# Xonik_Waveshaper_v1_0.net
KiCad netlist of a schematic drawn in EAGLE
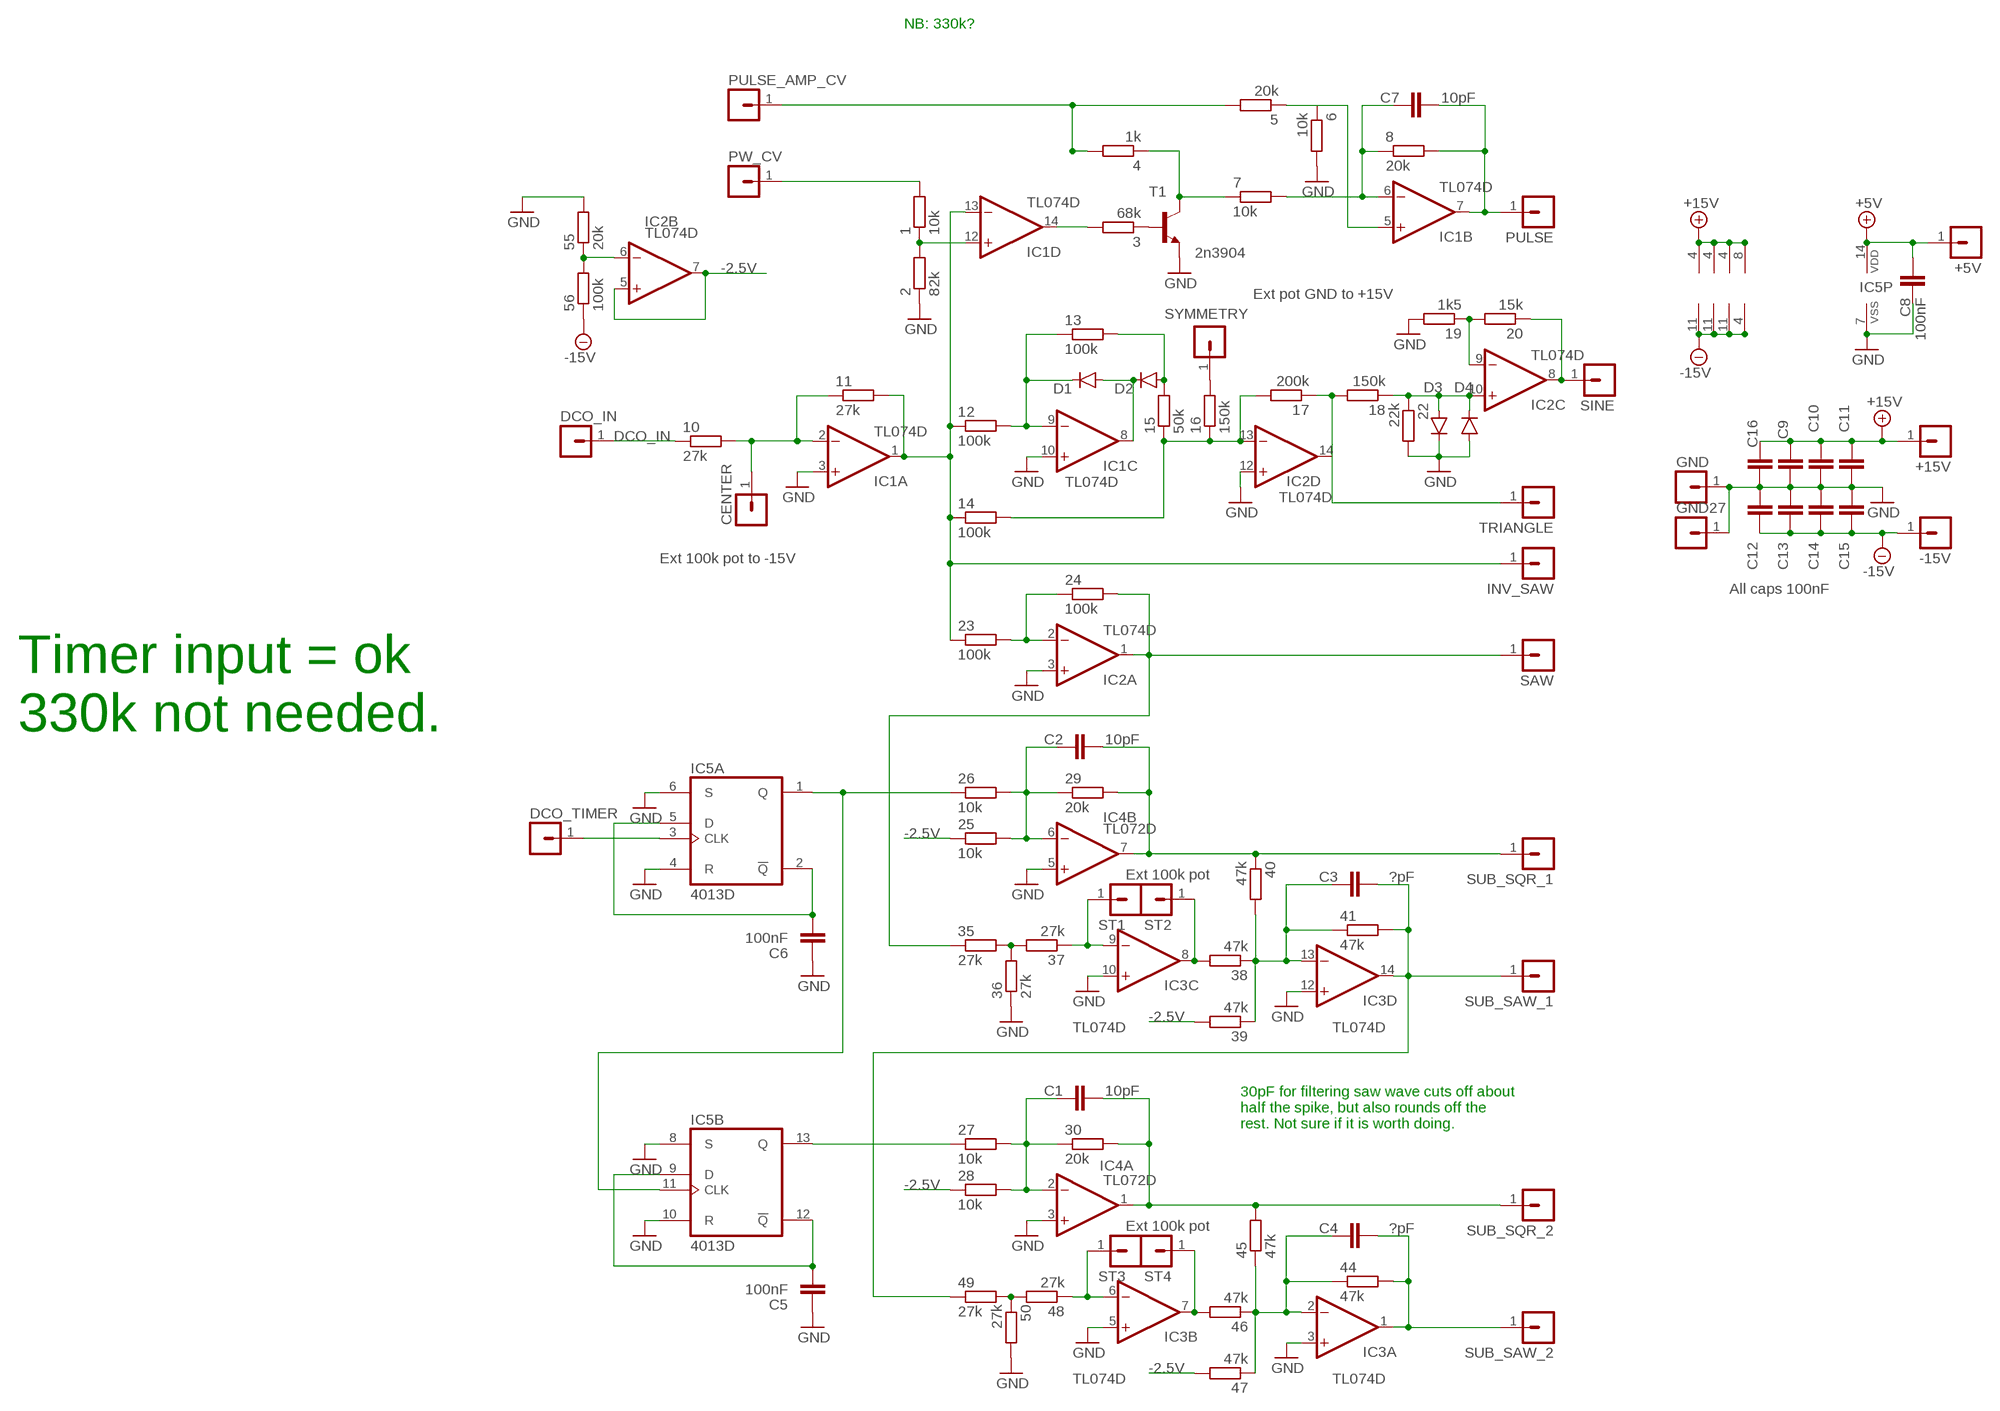
[diagram p0: schematic, sheet 1]

(export (version "E")
  (design (tool "Eeschema 10.0.6"))
  (components
    (comp (ref "+5V")
      (value "MA01-1JP")
      (footprint "eagle-import:SIP-PIN01-1J")
      (libsource (lib "eagle-import") (part "MA01-1JP"))
    )
    (comp (ref "+15V")
      (value "MA01-1JP")
      (footprint "eagle-import:SIP-PIN01-1J")
      (libsource (lib "eagle-import") (part "MA01-1JP"))
    )
    (comp (ref "-15V")
      (value "MA01-1JP")
      (footprint "eagle-import:SIP-PIN01-1J")
      (libsource (lib "eagle-import") (part "MA01-1JP"))
    )
    (comp (ref "1")
      (value "10k")
      (footprint "eagle-import:R0805")
      (libsource (lib "eagle-import") (part "R-EU_R0805"))
    )
    (comp (ref "2")
      (value "82k")
      (footprint "eagle-import:R0805")
      (libsource (lib "eagle-import") (part "R-EU_R0805"))
    )
    (comp (ref "3")
      (value "68k")
      (footprint "eagle-import:R0805")
      (libsource (lib "eagle-import") (part "R-EU_R0805"))
    )
    (comp (ref "4")
      (value "1k")
      (footprint "eagle-import:R0805")
      (libsource (lib "eagle-import") (part "R-EU_R0805"))
    )
    (comp (ref "5")
      (value "20k")
      (footprint "eagle-import:R0805")
      (libsource (lib "eagle-import") (part "R-EU_R0805"))
    )
    (comp (ref "6")
      (value "10k")
      (footprint "eagle-import:R0805")
      (libsource (lib "eagle-import") (part "R-EU_R0805"))
    )
    (comp (ref "7")
      (value "10k")
      (footprint "eagle-import:R0805")
      (libsource (lib "eagle-import") (part "R-EU_R0805"))
    )
    (comp (ref "8")
      (value "20k")
      (footprint "eagle-import:R0805")
      (libsource (lib "eagle-import") (part "R-EU_R0805"))
    )
    (comp (ref "10")
      (value "27k")
      (footprint "eagle-import:R0805")
      (libsource (lib "eagle-import") (part "R-EU_R0805"))
    )
    (comp (ref "11")
      (value "27k")
      (footprint "eagle-import:R0805")
      (libsource (lib "eagle-import") (part "R-EU_R0805"))
    )
    (comp (ref "12")
      (value "100k")
      (footprint "eagle-import:R0805")
      (libsource (lib "eagle-import") (part "R-EU_R0805"))
    )
    (comp (ref "13")
      (value "100k")
      (footprint "eagle-import:R0805")
      (libsource (lib "eagle-import") (part "R-EU_R0805"))
    )
    (comp (ref "14")
      (value "100k")
      (footprint "eagle-import:R0805")
      (libsource (lib "eagle-import") (part "R-EU_R0805"))
    )
    (comp (ref "15")
      (value "50k")
      (footprint "eagle-import:R0805")
      (libsource (lib "eagle-import") (part "R-EU_R0805"))
    )
    (comp (ref "16")
      (value "150k")
      (footprint "eagle-import:R0805")
      (libsource (lib "eagle-import") (part "R-EU_R0805"))
    )
    (comp (ref "17")
      (value "200k")
      (footprint "eagle-import:R0805")
      (libsource (lib "eagle-import") (part "R-EU_R0805"))
    )
    (comp (ref "18")
      (value "150k")
      (footprint "eagle-import:R0805")
      (libsource (lib "eagle-import") (part "R-EU_R0805"))
    )
    (comp (ref "19")
      (value "1k5")
      (footprint "eagle-import:R0805")
      (libsource (lib "eagle-import") (part "R-EU_R0805"))
    )
    (comp (ref "20")
      (value "15k")
      (footprint "eagle-import:R0805")
      (libsource (lib "eagle-import") (part "R-EU_R0805"))
    )
    (comp (ref "22")
      (value "22k")
      (footprint "eagle-import:R0805")
      (libsource (lib "eagle-import") (part "R-EU_R0805"))
    )
    (comp (ref "23")
      (value "100k")
      (footprint "eagle-import:R0805")
      (libsource (lib "eagle-import") (part "R-EU_R0805"))
    )
    (comp (ref "24")
      (value "100k")
      (footprint "eagle-import:R0805")
      (libsource (lib "eagle-import") (part "R-EU_R0805"))
    )
    (comp (ref "25")
      (value "10k")
      (footprint "eagle-import:R0805")
      (libsource (lib "eagle-import") (part "R-EU_R0805"))
    )
    (comp (ref "26")
      (value "10k")
      (footprint "eagle-import:R0805")
      (libsource (lib "eagle-import") (part "R-EU_R0805"))
    )
    (comp (ref "27")
      (value "10k")
      (footprint "eagle-import:R0805")
      (libsource (lib "eagle-import") (part "R-EU_R0805"))
    )
    (comp (ref "28")
      (value "10k")
      (footprint "eagle-import:R0805")
      (libsource (lib "eagle-import") (part "R-EU_R0805"))
    )
    (comp (ref "29")
      (value "20k")
      (footprint "eagle-import:R0805")
      (libsource (lib "eagle-import") (part "R-EU_R0805"))
    )
    (comp (ref "30")
      (value "20k")
      (footprint "eagle-import:R0805")
      (libsource (lib "eagle-import") (part "R-EU_R0805"))
    )
    (comp (ref "35")
      (value "27k")
      (footprint "eagle-import:R0805")
      (libsource (lib "eagle-import") (part "R-EU_R0805"))
    )
    (comp (ref "36")
      (value "27k")
      (footprint "eagle-import:R0805")
      (libsource (lib "eagle-import") (part "R-EU_R0805"))
    )
    (comp (ref "37")
      (value "27k")
      (footprint "eagle-import:R0805")
      (libsource (lib "eagle-import") (part "R-EU_R0805"))
    )
    (comp (ref "38")
      (value "47k")
      (footprint "eagle-import:R0805")
      (libsource (lib "eagle-import") (part "R-EU_R0805"))
    )
    (comp (ref "39")
      (value "47k")
      (footprint "eagle-import:R0805")
      (libsource (lib "eagle-import") (part "R-EU_R0805"))
    )
    (comp (ref "40")
      (value "47k")
      (footprint "eagle-import:R0805")
      (libsource (lib "eagle-import") (part "R-EU_R0805"))
    )
    (comp (ref "41")
      (value "47k")
      (footprint "eagle-import:R0805")
      (libsource (lib "eagle-import") (part "R-EU_R0805"))
    )
    (comp (ref "44")
      (value "47k")
      (footprint "eagle-import:R0805")
      (libsource (lib "eagle-import") (part "R-EU_R0805"))
    )
    (comp (ref "45")
      (value "47k")
      (footprint "eagle-import:R0805")
      (libsource (lib "eagle-import") (part "R-EU_R0805"))
    )
    (comp (ref "46")
      (value "47k")
      (footprint "eagle-import:R0805")
      (libsource (lib "eagle-import") (part "R-EU_R0805"))
    )
    (comp (ref "47")
      (value "47k")
      (footprint "eagle-import:R0805")
      (libsource (lib "eagle-import") (part "R-EU_R0805"))
    )
    (comp (ref "48")
      (value "27k")
      (footprint "eagle-import:R0805")
      (libsource (lib "eagle-import") (part "R-EU_R0805"))
    )
    (comp (ref "49")
      (value "27k")
      (footprint "eagle-import:R0805")
      (libsource (lib "eagle-import") (part "R-EU_R0805"))
    )
    (comp (ref "50")
      (value "27k")
      (footprint "eagle-import:R0805")
      (libsource (lib "eagle-import") (part "R-EU_R0805"))
    )
    (comp (ref "55")
      (value "20k")
      (footprint "eagle-import:R0805")
      (libsource (lib "eagle-import") (part "R-EU_R0805"))
    )
    (comp (ref "56")
      (value "100k")
      (footprint "eagle-import:R0805")
      (libsource (lib "eagle-import") (part "R-EU_R0805"))
    )
    (comp (ref "C1")
      (value "10pF")
      (footprint "eagle-import:C0805")
      (libsource (lib "eagle-import") (part "C-EUC0805"))
    )
    (comp (ref "C2")
      (value "10pF")
      (footprint "eagle-import:C0805")
      (libsource (lib "eagle-import") (part "C-EUC0805"))
    )
    (comp (ref "C3")
      (value "?pF")
      (footprint "eagle-import:C0805")
      (libsource (lib "eagle-import") (part "C-EUC0805"))
    )
    (comp (ref "C4")
      (value "?pF")
      (footprint "eagle-import:C0805")
      (libsource (lib "eagle-import") (part "C-EUC0805"))
    )
    (comp (ref "C5")
      (value "100nF")
      (footprint "eagle-import:C0805")
      (libsource (lib "eagle-import") (part "C-EUC0805"))
    )
    (comp (ref "C6")
      (value "100nF")
      (footprint "eagle-import:C0805")
      (libsource (lib "eagle-import") (part "C-EUC0805"))
    )
    (comp (ref "C7")
      (value "10pF")
      (footprint "eagle-import:C0805")
      (libsource (lib "eagle-import") (part "C-EUC0805"))
    )
    (comp (ref "C8")
      (value "100nF")
      (footprint "eagle-import:C0805")
      (libsource (lib "eagle-import") (part "C-EUC0805"))
    )
    (comp (ref "C9")
      (value "100nF")
      (footprint "eagle-import:C0603K")
      (libsource (lib "eagle-import") (part "C-EUC0603K"))
    )
    (comp (ref "C10")
      (value "100nF")
      (footprint "eagle-import:C0603K")
      (libsource (lib "eagle-import") (part "C-EUC0603K"))
    )
    (comp (ref "C11")
      (value "100nF")
      (footprint "eagle-import:C0603K")
      (libsource (lib "eagle-import") (part "C-EUC0603K"))
    )
    (comp (ref "C12")
      (value "100nF")
      (footprint "eagle-import:C0603K")
      (libsource (lib "eagle-import") (part "C-EUC0603K"))
    )
    (comp (ref "C13")
      (value "100nF")
      (footprint "eagle-import:C0603K")
      (libsource (lib "eagle-import") (part "C-EUC0603K"))
    )
    (comp (ref "C14")
      (value "100nF")
      (footprint "eagle-import:C0603K")
      (libsource (lib "eagle-import") (part "C-EUC0603K"))
    )
    (comp (ref "C15")
      (value "100nF")
      (footprint "eagle-import:C0603K")
      (libsource (lib "eagle-import") (part "C-EUC0603K"))
    )
    (comp (ref "C16")
      (value "100nF")
      (footprint "eagle-import:C0603K")
      (libsource (lib "eagle-import") (part "C-EUC0603K"))
    )
    (comp (ref "CENTER")
      (value "MA01-1JP")
      (footprint "eagle-import:SIP-PIN01-1J")
      (libsource (lib "eagle-import") (part "MA01-1JP"))
    )
    (comp (ref "D1")
      (value "1N41480805")
      (footprint "eagle-import:D0805-J")
      (libsource (lib "eagle-import") (part "1N41480805"))
    )
    (comp (ref "D2")
      (value "1N41480805")
      (footprint "eagle-import:D0805-J")
      (libsource (lib "eagle-import") (part "1N41480805"))
    )
    (comp (ref "D3")
      (value "1N41480805")
      (footprint "eagle-import:D0805-J")
      (libsource (lib "eagle-import") (part "1N41480805"))
    )
    (comp (ref "D4")
      (value "1N41480805")
      (footprint "eagle-import:D0805-J")
      (libsource (lib "eagle-import") (part "1N41480805"))
    )
    (comp (ref "DCO_IN")
      (value "MA01-1JP")
      (footprint "eagle-import:SIP-PIN01-1J")
      (libsource (lib "eagle-import") (part "MA01-1JP"))
    )
    (comp (ref "DCO_TIMER")
      (value "MA01-1JP")
      (footprint "eagle-import:SIP-PIN01-1J")
      (libsource (lib "eagle-import") (part "MA01-1JP"))
    )
    (comp (ref "GND")
      (value "MA01-1JP")
      (footprint "eagle-import:SIP-PIN01-1J")
      (libsource (lib "eagle-import") (part "MA01-1JP"))
    )
    (comp (ref "GND27")
      (value "MA01-1JP")
      (footprint "eagle-import:SIP-PIN01-1J")
      (libsource (lib "eagle-import") (part "MA01-1JP"))
    )
    (comp (ref "IC1")
      (value "TL074D")
      (footprint "eagle-import:SO14")
      (libsource (lib "eagle-import") (part "TL074D"))
    )
    (comp (ref "IC2")
      (value "TL074D")
      (footprint "eagle-import:SO14")
      (libsource (lib "eagle-import") (part "TL074D"))
    )
    (comp (ref "IC3")
      (value "TL074D")
      (footprint "eagle-import:SO14")
      (libsource (lib "eagle-import") (part "TL074D"))
    )
    (comp (ref "IC4")
      (value "TL072D")
      (footprint "eagle-import:SO08J")
      (libsource (lib "eagle-import") (part "TL072D"))
    )
    (comp (ref "IC5")
      (value "4013D")
      (footprint "eagle-import:SO14J")
      (libsource (lib "eagle-import") (part "4013D"))
    )
    (comp (ref "INV_SAW")
      (value "MA01-1JP")
      (footprint "eagle-import:SIP-PIN01-1J")
      (libsource (lib "eagle-import") (part "MA01-1JP"))
    )
    (comp (ref "PULSE")
      (value "MA01-1JP")
      (footprint "eagle-import:SIP-PIN01-1J")
      (libsource (lib "eagle-import") (part "MA01-1JP"))
    )
    (comp (ref "PULSE_AMP_CV")
      (value "MA01-1JP")
      (footprint "eagle-import:SIP-PIN01-1J")
      (libsource (lib "eagle-import") (part "MA01-1JP"))
    )
    (comp (ref "PW_CV")
      (value "MA01-1JP")
      (footprint "eagle-import:SIP-PIN01-1J")
      (libsource (lib "eagle-import") (part "MA01-1JP"))
    )
    (comp (ref "SAW")
      (value "MA01-1JP")
      (footprint "eagle-import:SIP-PIN01-1J")
      (libsource (lib "eagle-import") (part "MA01-1JP"))
    )
    (comp (ref "SINE")
      (value "MA01-1JP")
      (footprint "eagle-import:SIP-PIN01-1J")
      (libsource (lib "eagle-import") (part "MA01-1JP"))
    )
    (comp (ref "ST1")
      (value "MA01-1JP")
      (footprint "eagle-import:SIP-PIN01-1J")
      (libsource (lib "eagle-import") (part "MA01-1JP"))
    )
    (comp (ref "ST2")
      (value "MA01-1JP")
      (footprint "eagle-import:SIP-PIN01-1J")
      (libsource (lib "eagle-import") (part "MA01-1JP"))
    )
    (comp (ref "ST3")
      (value "MA01-1JP")
      (footprint "eagle-import:SIP-PIN01-1J")
      (libsource (lib "eagle-import") (part "MA01-1JP"))
    )
    (comp (ref "ST4")
      (value "MA01-1JP")
      (footprint "eagle-import:SIP-PIN01-1J")
      (libsource (lib "eagle-import") (part "MA01-1JP"))
    )
    (comp (ref "SUB_SAW_1")
      (value "MA01-1JP")
      (footprint "eagle-import:SIP-PIN01-1J")
      (libsource (lib "eagle-import") (part "MA01-1JP"))
    )
    (comp (ref "SUB_SAW_2")
      (value "MA01-1JP")
      (footprint "eagle-import:SIP-PIN01-1J")
      (libsource (lib "eagle-import") (part "MA01-1JP"))
    )
    (comp (ref "SUB_SQR_1")
      (value "MA01-1JP")
      (footprint "eagle-import:SIP-PIN01-1J")
      (libsource (lib "eagle-import") (part "MA01-1JP"))
    )
    (comp (ref "SUB_SQR_2")
      (value "MA01-1JP")
      (footprint "eagle-import:SIP-PIN01-1J")
      (libsource (lib "eagle-import") (part "MA01-1JP"))
    )
    (comp (ref "SYMMETRY")
      (value "MA01-1JP")
      (footprint "eagle-import:SIP-PIN01-1J")
      (libsource (lib "eagle-import") (part "MA01-1JP"))
    )
    (comp (ref "T1")
      (value "2n3904")
      (footprint "eagle-import:SOT23-BEC")
      (libsource (lib "eagle-import") (part "-NPN-SOT23-BECMMBT3904LT1"))
    )
    (comp (ref "TRIANGLE")
      (value "MA01-1JP")
      (footprint "eagle-import:SIP-PIN01-1J")
      (libsource (lib "eagle-import") (part "MA01-1JP"))
    )
  )
  (nets
    (net (code "1") (name "+5V") (class "Default")
      (node (ref "+5V") (pin "1") (pinfunction "1_1") (pintype "passive"))
      (node (ref "C8") (pin "2") (pinfunction "2_2") (pintype "passive"))
      (node (ref "IC5") (pin "14") (pinfunction "VDD_14") (pintype "power_in"))
    )
    (net (code "2") (name "+15V") (class "Default")
      (node (ref "+15V") (pin "1") (pinfunction "1_1") (pintype "passive"))
      (node (ref "C10") (pin "2") (pinfunction "2_2") (pintype "passive"))
      (node (ref "C11") (pin "2") (pinfunction "2_2") (pintype "passive"))
      (node (ref "C16") (pin "2") (pinfunction "2_2") (pintype "passive"))
      (node (ref "C9") (pin "2") (pinfunction "2_2") (pintype "passive"))
      (node (ref "IC1") (pin "4") (pinfunction "V+_4") (pintype "power_in"))
      (node (ref "IC2") (pin "4") (pinfunction "V+_4") (pintype "power_in"))
      (node (ref "IC3") (pin "4") (pinfunction "V+_4") (pintype "power_in"))
      (node (ref "IC4") (pin "8") (pinfunction "V+_8") (pintype "power_in"))
    )
    (net (code "3") (name "-15V") (class "Default")
      (node (ref "-15V") (pin "1") (pinfunction "1_1") (pintype "passive"))
      (node (ref "56") (pin "1") (pinfunction "1_1") (pintype "passive"))
      (node (ref "C12") (pin "1") (pinfunction "1_1") (pintype "passive"))
      (node (ref "C13") (pin "1") (pinfunction "1_1") (pintype "passive"))
      (node (ref "C14") (pin "1") (pinfunction "1_1") (pintype "passive"))
      (node (ref "C15") (pin "1") (pinfunction "1_1") (pintype "passive"))
      (node (ref "IC1") (pin "11") (pinfunction "V-_11") (pintype "power_in"))
      (node (ref "IC2") (pin "11") (pinfunction "V-_11") (pintype "power_in"))
      (node (ref "IC3") (pin "11") (pinfunction "V-_11") (pintype "power_in"))
      (node (ref "IC4") (pin "4") (pinfunction "V-_4") (pintype "power_in"))
    )
    (net (code "4") (name "/-2.5V") (class "Default")
      (node (ref "25") (pin "1") (pinfunction "1_1") (pintype "passive"))
      (node (ref "28") (pin "1") (pinfunction "1_1") (pintype "passive"))
      (node (ref "39") (pin "2") (pinfunction "2_2") (pintype "passive"))
      (node (ref "47") (pin "2") (pinfunction "2_2") (pintype "passive"))
      (node (ref "IC2") (pin "5") (pinfunction "+IN_5") (pintype "input"))
      (node (ref "IC2") (pin "7") (pinfunction "OUT_7") (pintype "output"))
    )
    (net (code "5") (name "/DCO_IN") (class "Default")
      (node (ref "10") (pin "1") (pinfunction "1_1") (pintype "passive"))
      (node (ref "DCO_IN") (pin "1") (pinfunction "1_1") (pintype "passive"))
    )
    (net (code "6") (name "GND") (class "Default")
      (node (ref "19") (pin "2") (pinfunction "2_2") (pintype "passive"))
      (node (ref "2") (pin "1") (pinfunction "1_1") (pintype "passive"))
      (node (ref "22") (pin "2") (pinfunction "2_2") (pintype "passive"))
      (node (ref "36") (pin "1") (pinfunction "1_1") (pintype "passive"))
      (node (ref "50") (pin "2") (pinfunction "2_2") (pintype "passive"))
      (node (ref "55") (pin "2") (pinfunction "2_2") (pintype "passive"))
      (node (ref "6") (pin "2") (pinfunction "2_2") (pintype "passive"))
      (node (ref "C10") (pin "1") (pinfunction "1_1") (pintype "passive"))
      (node (ref "C11") (pin "1") (pinfunction "1_1") (pintype "passive"))
      (node (ref "C12") (pin "2") (pinfunction "2_2") (pintype "passive"))
      (node (ref "C13") (pin "2") (pinfunction "2_2") (pintype "passive"))
      (node (ref "C14") (pin "2") (pinfunction "2_2") (pintype "passive"))
      (node (ref "C15") (pin "2") (pinfunction "2_2") (pintype "passive"))
      (node (ref "C16") (pin "1") (pinfunction "1_1") (pintype "passive"))
      (node (ref "C5") (pin "1") (pinfunction "1_1") (pintype "passive"))
      (node (ref "C6") (pin "1") (pinfunction "1_1") (pintype "passive"))
      (node (ref "C8") (pin "1") (pinfunction "1_1") (pintype "passive"))
      (node (ref "C9") (pin "1") (pinfunction "1_1") (pintype "passive"))
      (node (ref "D3") (pin "C") (pinfunction "C_C") (pintype "passive"))
      (node (ref "D4") (pin "A") (pinfunction "A_A") (pintype "passive"))
      (node (ref "GND") (pin "1") (pinfunction "1_1") (pintype "passive"))
      (node (ref "GND27") (pin "1") (pinfunction "1_1") (pintype "passive"))
      (node (ref "IC1") (pin "10") (pinfunction "+IN_10") (pintype "input"))
      (node (ref "IC1") (pin "3") (pinfunction "+IN_3") (pintype "input"))
      (node (ref "IC2") (pin "12") (pinfunction "+IN_12") (pintype "input"))
      (node (ref "IC2") (pin "3") (pinfunction "+IN_3") (pintype "input"))
      (node (ref "IC3") (pin "10") (pinfunction "+IN_10") (pintype "input"))
      (node (ref "IC3") (pin "12") (pinfunction "+IN_12") (pintype "input"))
      (node (ref "IC3") (pin "3") (pinfunction "+IN_3") (pintype "input"))
      (node (ref "IC3") (pin "5") (pinfunction "+IN_5") (pintype "input"))
      (node (ref "IC4") (pin "3") (pinfunction "+IN_3") (pintype "input"))
      (node (ref "IC4") (pin "5") (pinfunction "+IN_5") (pintype "input"))
      (node (ref "IC5") (pin "10") (pinfunction "R_10") (pintype "input"))
      (node (ref "IC5") (pin "4") (pinfunction "R_4") (pintype "input"))
      (node (ref "IC5") (pin "6") (pinfunction "S_6") (pintype "input"))
      (node (ref "IC5") (pin "7") (pinfunction "VSS_7") (pintype "power_in"))
      (node (ref "IC5") (pin "8") (pinfunction "S_8") (pintype "input"))
      (node (ref "T1") (pin "E") (pinfunction "E_E") (pintype "passive"))
    )
    (net (code "7") (name "Net-(1-Pad2)") (class "Default")
      (node (ref "1") (pin "2") (pinfunction "2_2") (pintype "passive"))
      (node (ref "PW_CV") (pin "1") (pinfunction "1_1") (pintype "passive"))
    )
    (net (code "8") (name "Net-(3-Pad1)") (class "Default")
      (node (ref "3") (pin "1") (pinfunction "1_1") (pintype "passive"))
      (node (ref "T1") (pin "B") (pinfunction "B_B") (pintype "passive"))
    )
    (net (code "9") (name "Net-(4-Pad1)") (class "Default")
      (node (ref "4") (pin "1") (pinfunction "1_1") (pintype "passive"))
      (node (ref "7") (pin "1") (pinfunction "1_1") (pintype "passive"))
      (node (ref "T1") (pin "C") (pinfunction "C_C") (pintype "passive"))
    )
    (net (code "10") (name "Net-(4-Pad2)") (class "Default")
      (node (ref "4") (pin "2") (pinfunction "2_2") (pintype "passive"))
      (node (ref "5") (pin "2") (pinfunction "2_2") (pintype "passive"))
      (node (ref "PULSE_AMP_CV") (pin "1") (pinfunction "1_1") (pintype "passive"))
    )
    (net (code "11") (name "Net-(13-Pad2)") (class "Default")
      (node (ref "13") (pin "2") (pinfunction "2_2") (pintype "passive"))
      (node (ref "15") (pin "2") (pinfunction "2_2") (pintype "passive"))
      (node (ref "D2") (pin "A") (pinfunction "A_A") (pintype "passive"))
    )
    (net (code "12") (name "Net-(16-Pad2)") (class "Default")
      (node (ref "16") (pin "2") (pinfunction "2_2") (pintype "passive"))
      (node (ref "SYMMETRY") (pin "1") (pinfunction "1_1") (pintype "passive"))
    )
    (net (code "13") (name "Net-(35-Pad2)") (class "Default")
      (node (ref "35") (pin "2") (pinfunction "2_2") (pintype "passive"))
      (node (ref "36") (pin "2") (pinfunction "2_2") (pintype "passive"))
      (node (ref "37") (pin "2") (pinfunction "2_2") (pintype "passive"))
    )
    (net (code "14") (name "Net-(48-Pad2)") (class "Default")
      (node (ref "48") (pin "2") (pinfunction "2_2") (pintype "passive"))
      (node (ref "49") (pin "2") (pinfunction "2_2") (pintype "passive"))
      (node (ref "50") (pin "1") (pinfunction "1_1") (pintype "passive"))
    )
    (net (code "15") (name "Net-(IC1A--IN)") (class "Default")
      (node (ref "10") (pin "2") (pinfunction "2_2") (pintype "passive"))
      (node (ref "11") (pin "1") (pinfunction "1_1") (pintype "passive"))
      (node (ref "CENTER") (pin "1") (pinfunction "1_1") (pintype "passive"))
      (node (ref "IC1") (pin "2") (pinfunction "-IN_2") (pintype "input"))
    )
    (net (code "16") (name "Net-(IC1A-OUT)") (class "Default")
      (node (ref "11") (pin "2") (pinfunction "2_2") (pintype "passive"))
      (node (ref "12") (pin "1") (pinfunction "1_1") (pintype "passive"))
      (node (ref "14") (pin "1") (pinfunction "1_1") (pintype "passive"))
      (node (ref "23") (pin "1") (pinfunction "1_1") (pintype "passive"))
      (node (ref "IC1") (pin "1") (pinfunction "OUT_1") (pintype "output"))
      (node (ref "IC1") (pin "13") (pinfunction "-IN_13") (pintype "input"))
      (node (ref "INV_SAW") (pin "1") (pinfunction "1_1") (pintype "passive"))
    )
    (net (code "17") (name "Net-(IC1B-+IN)") (class "Default")
      (node (ref "5") (pin "1") (pinfunction "1_1") (pintype "passive"))
      (node (ref "6") (pin "1") (pinfunction "1_1") (pintype "passive"))
      (node (ref "IC1") (pin "5") (pinfunction "+IN_5") (pintype "input"))
    )
    (net (code "18") (name "Net-(IC1B--IN)") (class "Default")
      (node (ref "7") (pin "2") (pinfunction "2_2") (pintype "passive"))
      (node (ref "8") (pin "1") (pinfunction "1_1") (pintype "passive"))
      (node (ref "C7") (pin "1") (pinfunction "1_1") (pintype "passive"))
      (node (ref "IC1") (pin "6") (pinfunction "-IN_6") (pintype "input"))
    )
    (net (code "19") (name "Net-(IC1B-OUT)") (class "Default")
      (node (ref "8") (pin "2") (pinfunction "2_2") (pintype "passive"))
      (node (ref "C7") (pin "2") (pinfunction "2_2") (pintype "passive"))
      (node (ref "IC1") (pin "7") (pinfunction "OUT_7") (pintype "output"))
      (node (ref "PULSE") (pin "1") (pinfunction "1_1") (pintype "passive"))
    )
    (net (code "20") (name "Net-(IC1C--IN)") (class "Default")
      (node (ref "12") (pin "2") (pinfunction "2_2") (pintype "passive"))
      (node (ref "13") (pin "1") (pinfunction "1_1") (pintype "passive"))
      (node (ref "D1") (pin "C") (pinfunction "C_C") (pintype "passive"))
      (node (ref "IC1") (pin "9") (pinfunction "-IN_9") (pintype "input"))
    )
    (net (code "21") (name "Net-(IC1C-OUT)") (class "Default")
      (node (ref "D1") (pin "A") (pinfunction "A_A") (pintype "passive"))
      (node (ref "D2") (pin "C") (pinfunction "C_C") (pintype "passive"))
      (node (ref "IC1") (pin "8") (pinfunction "OUT_8") (pintype "output"))
    )
    (net (code "22") (name "Net-(IC1D-+IN)") (class "Default")
      (node (ref "1") (pin "1") (pinfunction "1_1") (pintype "passive"))
      (node (ref "2") (pin "2") (pinfunction "2_2") (pintype "passive"))
      (node (ref "IC1") (pin "12") (pinfunction "+IN_12") (pintype "input"))
    )
    (net (code "23") (name "Net-(IC1D-OUT)") (class "Default")
      (node (ref "3") (pin "2") (pinfunction "2_2") (pintype "passive"))
      (node (ref "IC1") (pin "14") (pinfunction "OUT_14") (pintype "output"))
    )
    (net (code "24") (name "Net-(IC2A--IN)") (class "Default")
      (node (ref "23") (pin "2") (pinfunction "2_2") (pintype "passive"))
      (node (ref "24") (pin "1") (pinfunction "1_1") (pintype "passive"))
      (node (ref "IC2") (pin "2") (pinfunction "-IN_2") (pintype "input"))
    )
    (net (code "25") (name "Net-(IC2A-OUT)") (class "Default")
      (node (ref "24") (pin "2") (pinfunction "2_2") (pintype "passive"))
      (node (ref "35") (pin "1") (pinfunction "1_1") (pintype "passive"))
      (node (ref "IC2") (pin "1") (pinfunction "OUT_1") (pintype "output"))
      (node (ref "SAW") (pin "1") (pinfunction "1_1") (pintype "passive"))
    )
    (net (code "26") (name "Net-(IC2B--IN)") (class "Default")
      (node (ref "55") (pin "1") (pinfunction "1_1") (pintype "passive"))
      (node (ref "56") (pin "2") (pinfunction "2_2") (pintype "passive"))
      (node (ref "IC2") (pin "6") (pinfunction "-IN_6") (pintype "input"))
    )
    (net (code "27") (name "Net-(IC2C-+IN)") (class "Default")
      (node (ref "18") (pin "1") (pinfunction "1_1") (pintype "passive"))
      (node (ref "22") (pin "1") (pinfunction "1_1") (pintype "passive"))
      (node (ref "D3") (pin "A") (pinfunction "A_A") (pintype "passive"))
      (node (ref "D4") (pin "C") (pinfunction "C_C") (pintype "passive"))
      (node (ref "IC2") (pin "10") (pinfunction "+IN_10") (pintype "input"))
    )
    (net (code "28") (name "Net-(IC2C--IN)") (class "Default")
      (node (ref "19") (pin "1") (pinfunction "1_1") (pintype "passive"))
      (node (ref "20") (pin "2") (pinfunction "2_2") (pintype "passive"))
      (node (ref "IC2") (pin "9") (pinfunction "-IN_9") (pintype "input"))
    )
    (net (code "29") (name "Net-(IC2C-OUT)") (class "Default")
      (node (ref "20") (pin "1") (pinfunction "1_1") (pintype "passive"))
      (node (ref "IC2") (pin "8") (pinfunction "OUT_8") (pintype "output"))
      (node (ref "SINE") (pin "1") (pinfunction "1_1") (pintype "passive"))
    )
    (net (code "30") (name "Net-(IC2D--IN)") (class "Default")
      (node (ref "14") (pin "2") (pinfunction "2_2") (pintype "passive"))
      (node (ref "15") (pin "1") (pinfunction "1_1") (pintype "passive"))
      (node (ref "16") (pin "1") (pinfunction "1_1") (pintype "passive"))
      (node (ref "17") (pin "2") (pinfunction "2_2") (pintype "passive"))
      (node (ref "IC2") (pin "13") (pinfunction "-IN_13") (pintype "input"))
    )
    (net (code "31") (name "Net-(IC2D-OUT)") (class "Default")
      (node (ref "17") (pin "1") (pinfunction "1_1") (pintype "passive"))
      (node (ref "18") (pin "2") (pinfunction "2_2") (pintype "passive"))
      (node (ref "IC2") (pin "14") (pinfunction "OUT_14") (pintype "output"))
      (node (ref "TRIANGLE") (pin "1") (pinfunction "1_1") (pintype "passive"))
    )
    (net (code "32") (name "Net-(IC3A--IN)") (class "Default")
      (node (ref "44") (pin "1") (pinfunction "1_1") (pintype "passive"))
      (node (ref "45") (pin "1") (pinfunction "1_1") (pintype "passive"))
      (node (ref "46") (pin "1") (pinfunction "1_1") (pintype "passive"))
      (node (ref "47") (pin "1") (pinfunction "1_1") (pintype "passive"))
      (node (ref "C4") (pin "1") (pinfunction "1_1") (pintype "passive"))
      (node (ref "IC3") (pin "2") (pinfunction "-IN_2") (pintype "input"))
    )
    (net (code "33") (name "Net-(IC3A-OUT)") (class "Default")
      (node (ref "44") (pin "2") (pinfunction "2_2") (pintype "passive"))
      (node (ref "C4") (pin "2") (pinfunction "2_2") (pintype "passive"))
      (node (ref "IC3") (pin "1") (pinfunction "OUT_1") (pintype "output"))
      (node (ref "SUB_SAW_2") (pin "1") (pinfunction "1_1") (pintype "passive"))
    )
    (net (code "34") (name "Net-(IC3B--IN)") (class "Default")
      (node (ref "48") (pin "1") (pinfunction "1_1") (pintype "passive"))
      (node (ref "IC3") (pin "6") (pinfunction "-IN_6") (pintype "input"))
      (node (ref "ST3") (pin "1") (pinfunction "1_1") (pintype "passive"))
    )
    (net (code "35") (name "Net-(IC3B-OUT)") (class "Default")
      (node (ref "46") (pin "2") (pinfunction "2_2") (pintype "passive"))
      (node (ref "IC3") (pin "7") (pinfunction "OUT_7") (pintype "output"))
      (node (ref "ST4") (pin "1") (pinfunction "1_1") (pintype "passive"))
    )
    (net (code "36") (name "Net-(IC3C--IN)") (class "Default")
      (node (ref "37") (pin "1") (pinfunction "1_1") (pintype "passive"))
      (node (ref "IC3") (pin "9") (pinfunction "-IN_9") (pintype "input"))
      (node (ref "ST1") (pin "1") (pinfunction "1_1") (pintype "passive"))
    )
    (net (code "37") (name "Net-(IC3C-OUT)") (class "Default")
      (node (ref "38") (pin "2") (pinfunction "2_2") (pintype "passive"))
      (node (ref "IC3") (pin "8") (pinfunction "OUT_8") (pintype "output"))
      (node (ref "ST2") (pin "1") (pinfunction "1_1") (pintype "passive"))
    )
    (net (code "38") (name "Net-(IC3D--IN)") (class "Default")
      (node (ref "38") (pin "1") (pinfunction "1_1") (pintype "passive"))
      (node (ref "39") (pin "1") (pinfunction "1_1") (pintype "passive"))
      (node (ref "40") (pin "2") (pinfunction "2_2") (pintype "passive"))
      (node (ref "41") (pin "1") (pinfunction "1_1") (pintype "passive"))
      (node (ref "C3") (pin "1") (pinfunction "1_1") (pintype "passive"))
      (node (ref "IC3") (pin "13") (pinfunction "-IN_13") (pintype "input"))
    )
    (net (code "39") (name "Net-(IC3D-OUT)") (class "Default")
      (node (ref "41") (pin "2") (pinfunction "2_2") (pintype "passive"))
      (node (ref "49") (pin "1") (pinfunction "1_1") (pintype "passive"))
      (node (ref "C3") (pin "2") (pinfunction "2_2") (pintype "passive"))
      (node (ref "IC3") (pin "14") (pinfunction "OUT_14") (pintype "output"))
      (node (ref "SUB_SAW_1") (pin "1") (pinfunction "1_1") (pintype "passive"))
    )
    (net (code "40") (name "Net-(IC4A--IN)") (class "Default")
      (node (ref "27") (pin "2") (pinfunction "2_2") (pintype "passive"))
      (node (ref "28") (pin "2") (pinfunction "2_2") (pintype "passive"))
      (node (ref "30") (pin "1") (pinfunction "1_1") (pintype "passive"))
      (node (ref "C1") (pin "1") (pinfunction "1_1") (pintype "passive"))
      (node (ref "IC4") (pin "2") (pinfunction "-IN_2") (pintype "input"))
    )
    (net (code "41") (name "Net-(IC4A-OUT)") (class "Default")
      (node (ref "30") (pin "2") (pinfunction "2_2") (pintype "passive"))
      (node (ref "45") (pin "2") (pinfunction "2_2") (pintype "passive"))
      (node (ref "C1") (pin "2") (pinfunction "2_2") (pintype "passive"))
      (node (ref "IC4") (pin "1") (pinfunction "OUT_1") (pintype "output"))
      (node (ref "SUB_SQR_2") (pin "1") (pinfunction "1_1") (pintype "passive"))
    )
    (net (code "42") (name "Net-(IC4B--IN)") (class "Default")
      (node (ref "25") (pin "2") (pinfunction "2_2") (pintype "passive"))
      (node (ref "26") (pin "2") (pinfunction "2_2") (pintype "passive"))
      (node (ref "29") (pin "1") (pinfunction "1_1") (pintype "passive"))
      (node (ref "C2") (pin "1") (pinfunction "1_1") (pintype "passive"))
      (node (ref "IC4") (pin "6") (pinfunction "-IN_6") (pintype "input"))
    )
    (net (code "43") (name "Net-(IC4B-OUT)") (class "Default")
      (node (ref "29") (pin "2") (pinfunction "2_2") (pintype "passive"))
      (node (ref "40") (pin "1") (pinfunction "1_1") (pintype "passive"))
      (node (ref "C2") (pin "2") (pinfunction "2_2") (pintype "passive"))
      (node (ref "IC4") (pin "7") (pinfunction "OUT_7") (pintype "output"))
      (node (ref "SUB_SQR_1") (pin "1") (pinfunction "1_1") (pintype "passive"))
    )
    (net (code "44") (name "Net-(IC5A-CLK)") (class "Default")
      (node (ref "DCO_TIMER") (pin "1") (pinfunction "1_1") (pintype "passive"))
      (node (ref "IC5") (pin "3") (pinfunction "CLK_3") (pintype "input"))
    )
    (net (code "45") (name "Net-(IC5A-D)") (class "Default")
      (node (ref "C6") (pin "2") (pinfunction "2_2") (pintype "passive"))
      (node (ref "IC5") (pin "2") (pinfunction "~{Q}_2") (pintype "output"))
      (node (ref "IC5") (pin "5") (pinfunction "D_5") (pintype "input"))
    )
    (net (code "46") (name "Net-(IC5A-Q)") (class "Default")
      (node (ref "26") (pin "1") (pinfunction "1_1") (pintype "passive"))
      (node (ref "IC5") (pin "1") (pinfunction "Q_1") (pintype "output"))
      (node (ref "IC5") (pin "11") (pinfunction "CLK_11") (pintype "input"))
    )
    (net (code "47") (name "Net-(IC5B-D)") (class "Default")
      (node (ref "C5") (pin "2") (pinfunction "2_2") (pintype "passive"))
      (node (ref "IC5") (pin "12") (pinfunction "~{Q}_12") (pintype "output"))
      (node (ref "IC5") (pin "9") (pinfunction "D_9") (pintype "input"))
    )
    (net (code "48") (name "Net-(IC5B-Q)") (class "Default")
      (node (ref "27") (pin "1") (pinfunction "1_1") (pintype "passive"))
      (node (ref "IC5") (pin "13") (pinfunction "Q_13") (pintype "output"))
    )
  )
)
